# isoJTAG.net
KiCad netlist of a schematic drawn in Altium Designer
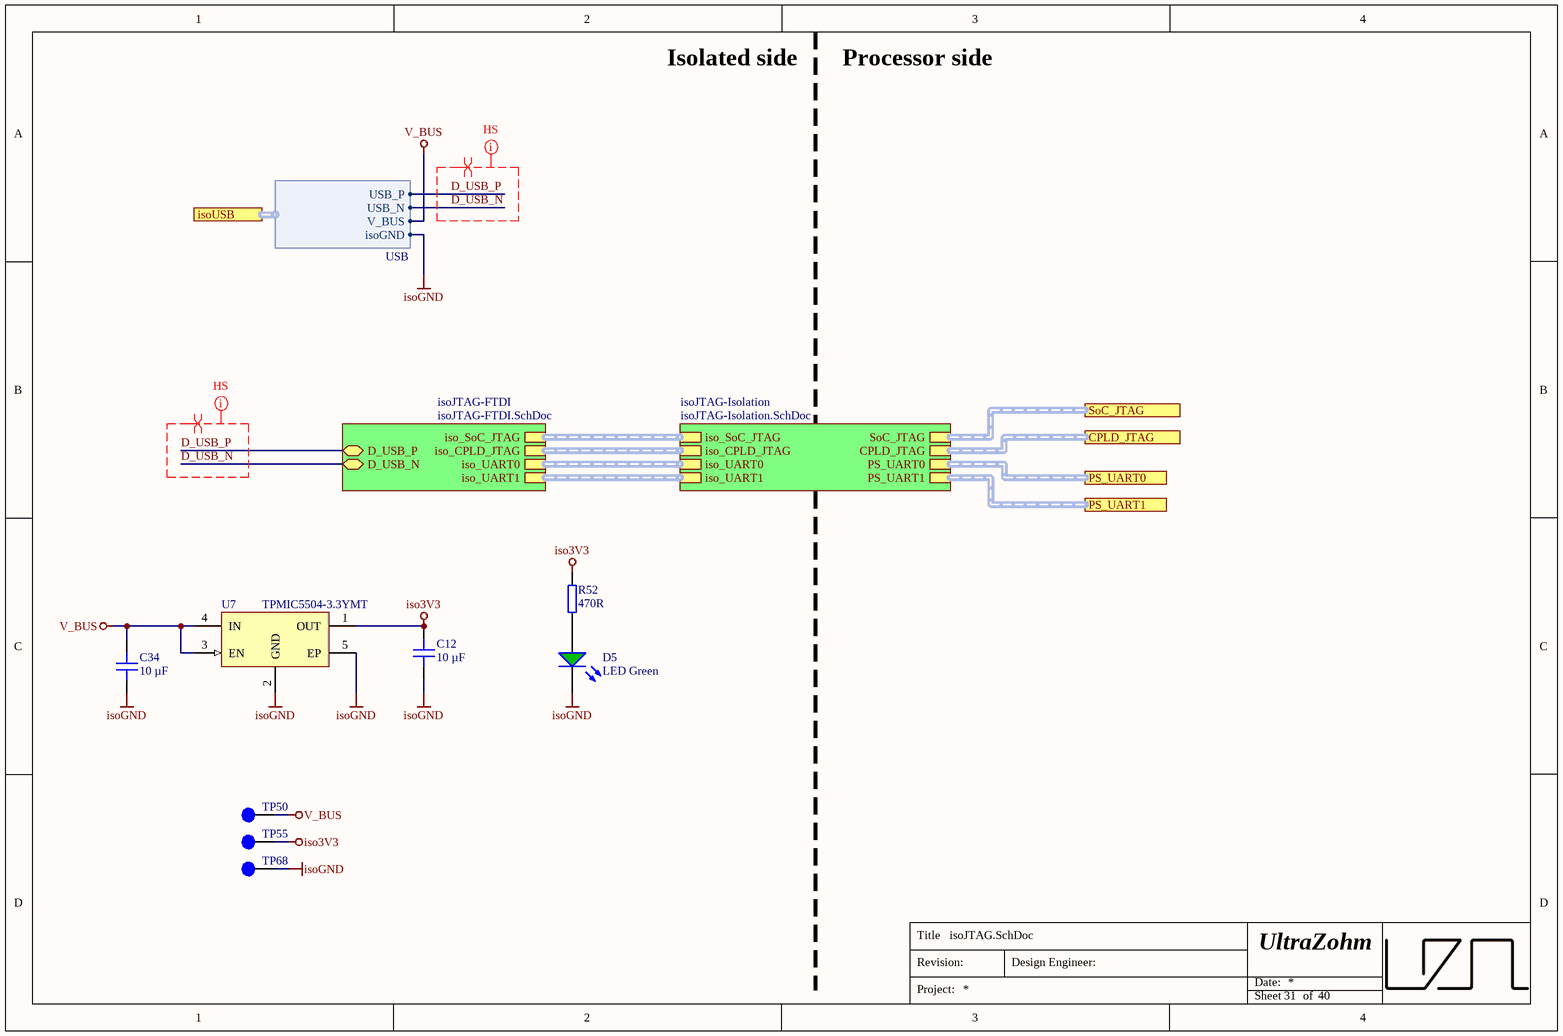
[diagram p0: isoJTAG.SchDoc]

(export (version "E")
  (design (tool "Eeschema 10.0.6"))
  (components
    (comp (ref "C12")
      (value "10 µF")
      (footprint "C_0603")
      (description "Capacitor 0603, 16 VDC, 10 µF, X5R")
      (fields
        (field (name "MANUFACTURER PART NUMBER") "CL10A106MO8NQNC")
        (field (name "MANUFACTURER") "Samsung Electro-Mechanics")
        (field (name "CREATED FROM") "AGeiger")
      )
      (libsource (lib "user") (part "Capacitor"))
    )
    (comp (ref "C34")
      (value "10 µF")
      (footprint "C_0603")
      (description "Capacitor 0603, 16 VDC, 10 µF, X5R")
      (fields
        (field (name "MANUFACTURER PART NUMBER") "CL10A106MO8NQNC")
        (field (name "MANUFACTURER") "Samsung Electro-Mechanics")
        (field (name "CREATED FROM") "AGeiger")
      )
      (libsource (lib "user") (part "Capacitor"))
    )
    (comp (ref "D5")
      (value "LED Green")
      (footprint "WL-SMCW_0603")
      (description "Standard LEDs - SMD 0603 green")
      (fields
        (field (name "MANUFACTURER PART NUMBER") "UZgen_LED_0603_Green")
        (field (name "MANUFACTURER") "UZgen")
        (field (name "CREATED FROM") "UZgenTool")
      )
      (libsource (lib "user") (part "LED_Green"))
    )
    (comp (ref "R52")
      (value "470R")
      (footprint "R_0603_TE")
      (description "Generic resistor")
      (fields
        (field (name "MANUFACTURER PART NUMBER") "UZgen_R_0603_470R")
        (field (name "MANUFACTURER") "UZgen")
        (field (name "CREATED FROM") "UZgenTool")
      )
      (libsource (lib "user") (part "RES"))
    )
    (comp (ref "TP50")
      (value "Testpoint 1mm")
      (footprint "TP_1mm")
      (fields
        (field (name "MANUFACTURER PART NUMBER") "NULL")
        (field (name "CREATED") "2018_06_25_AGeiger")
        (field (name "CREATED FROM") "AGeiger")
      )
      (libsource (lib "user") (part "TP_1mm"))
    )
    (comp (ref "TP55")
      (value "Testpoint 1mm")
      (footprint "TP_1mm")
      (fields
        (field (name "MANUFACTURER PART NUMBER") "NULL")
        (field (name "CREATED") "2018_06_25_AGeiger")
        (field (name "CREATED FROM") "AGeiger")
      )
      (libsource (lib "user") (part "TP_1mm"))
    )
    (comp (ref "TP68")
      (value "Testpoint 1mm")
      (footprint "TP_1mm")
      (fields
        (field (name "MANUFACTURER PART NUMBER") "NULL")
        (field (name "CREATED") "2018_06_25_AGeiger")
        (field (name "CREATED FROM") "AGeiger")
      )
      (libsource (lib "user") (part "TP_1mm"))
    )
    (comp (ref "U7")
      (value "TPMIC5504-3.3YMT")
      (footprint "DFN-4-EP")
      (description "DFN-4-EP(1x1) Linear Voltage Regulators (LDO) ROHS")
      (fields
        (field (name "MANUFACTURER") "TECH PUBLIC")
        (field (name "LCSC PART NUMBER") "C3021135")
        (field (name "CREATED FROM") "AGeiger")
      )
      (libsource (lib "user") (part "TPMIC5504-3.3YMT"))
    )
  )
  (nets
    (net (code "17") (name "Net-(D5-A)") (class "Default")
      (node (ref "D5") (pin "2") (pinfunction "A_2") (pintype "passive"))
      (node (ref "R52") (pin "1") (pinfunction "1_1") (pintype "passive"))
    )
    (net (code "18") (name "V_BUS") (class "Default")
      (node (ref "C34") (pin "2") (pinfunction "2_2") (pintype "passive"))
      (node (ref "TP50") (pin "1") (pintype "passive"))
      (node (ref "U7") (pin "3") (pinfunction "EN_3") (pintype "input"))
      (node (ref "U7") (pin "4") (pinfunction "IN_4") (pintype "power_in"))
    )
    (net (code "19") (name "iso3V3") (class "Default")
      (node (ref "C12") (pin "2") (pinfunction "2_2") (pintype "passive"))
      (node (ref "R52") (pin "2") (pinfunction "2_2") (pintype "passive"))
      (node (ref "TP55") (pin "1") (pintype "passive"))
      (node (ref "U7") (pin "1") (pinfunction "OUT_1") (pintype "power_in"))
    )
    (net (code "20") (name "isoGND") (class "Default")
      (node (ref "C12") (pin "1") (pinfunction "1_1") (pintype "passive"))
      (node (ref "C34") (pin "1") (pinfunction "1_1") (pintype "passive"))
      (node (ref "D5") (pin "1") (pinfunction "K_1") (pintype "passive"))
      (node (ref "TP68") (pin "1") (pintype "passive"))
      (node (ref "U7") (pin "2") (pinfunction "GND_2") (pintype "power_in"))
      (node (ref "U7") (pin "5") (pinfunction "EP_5") (pintype "power_in"))
    )
  )
)
